# lab2_kochurin_buck.net
KiCad netlist of a schematic drawn in Altium Designer
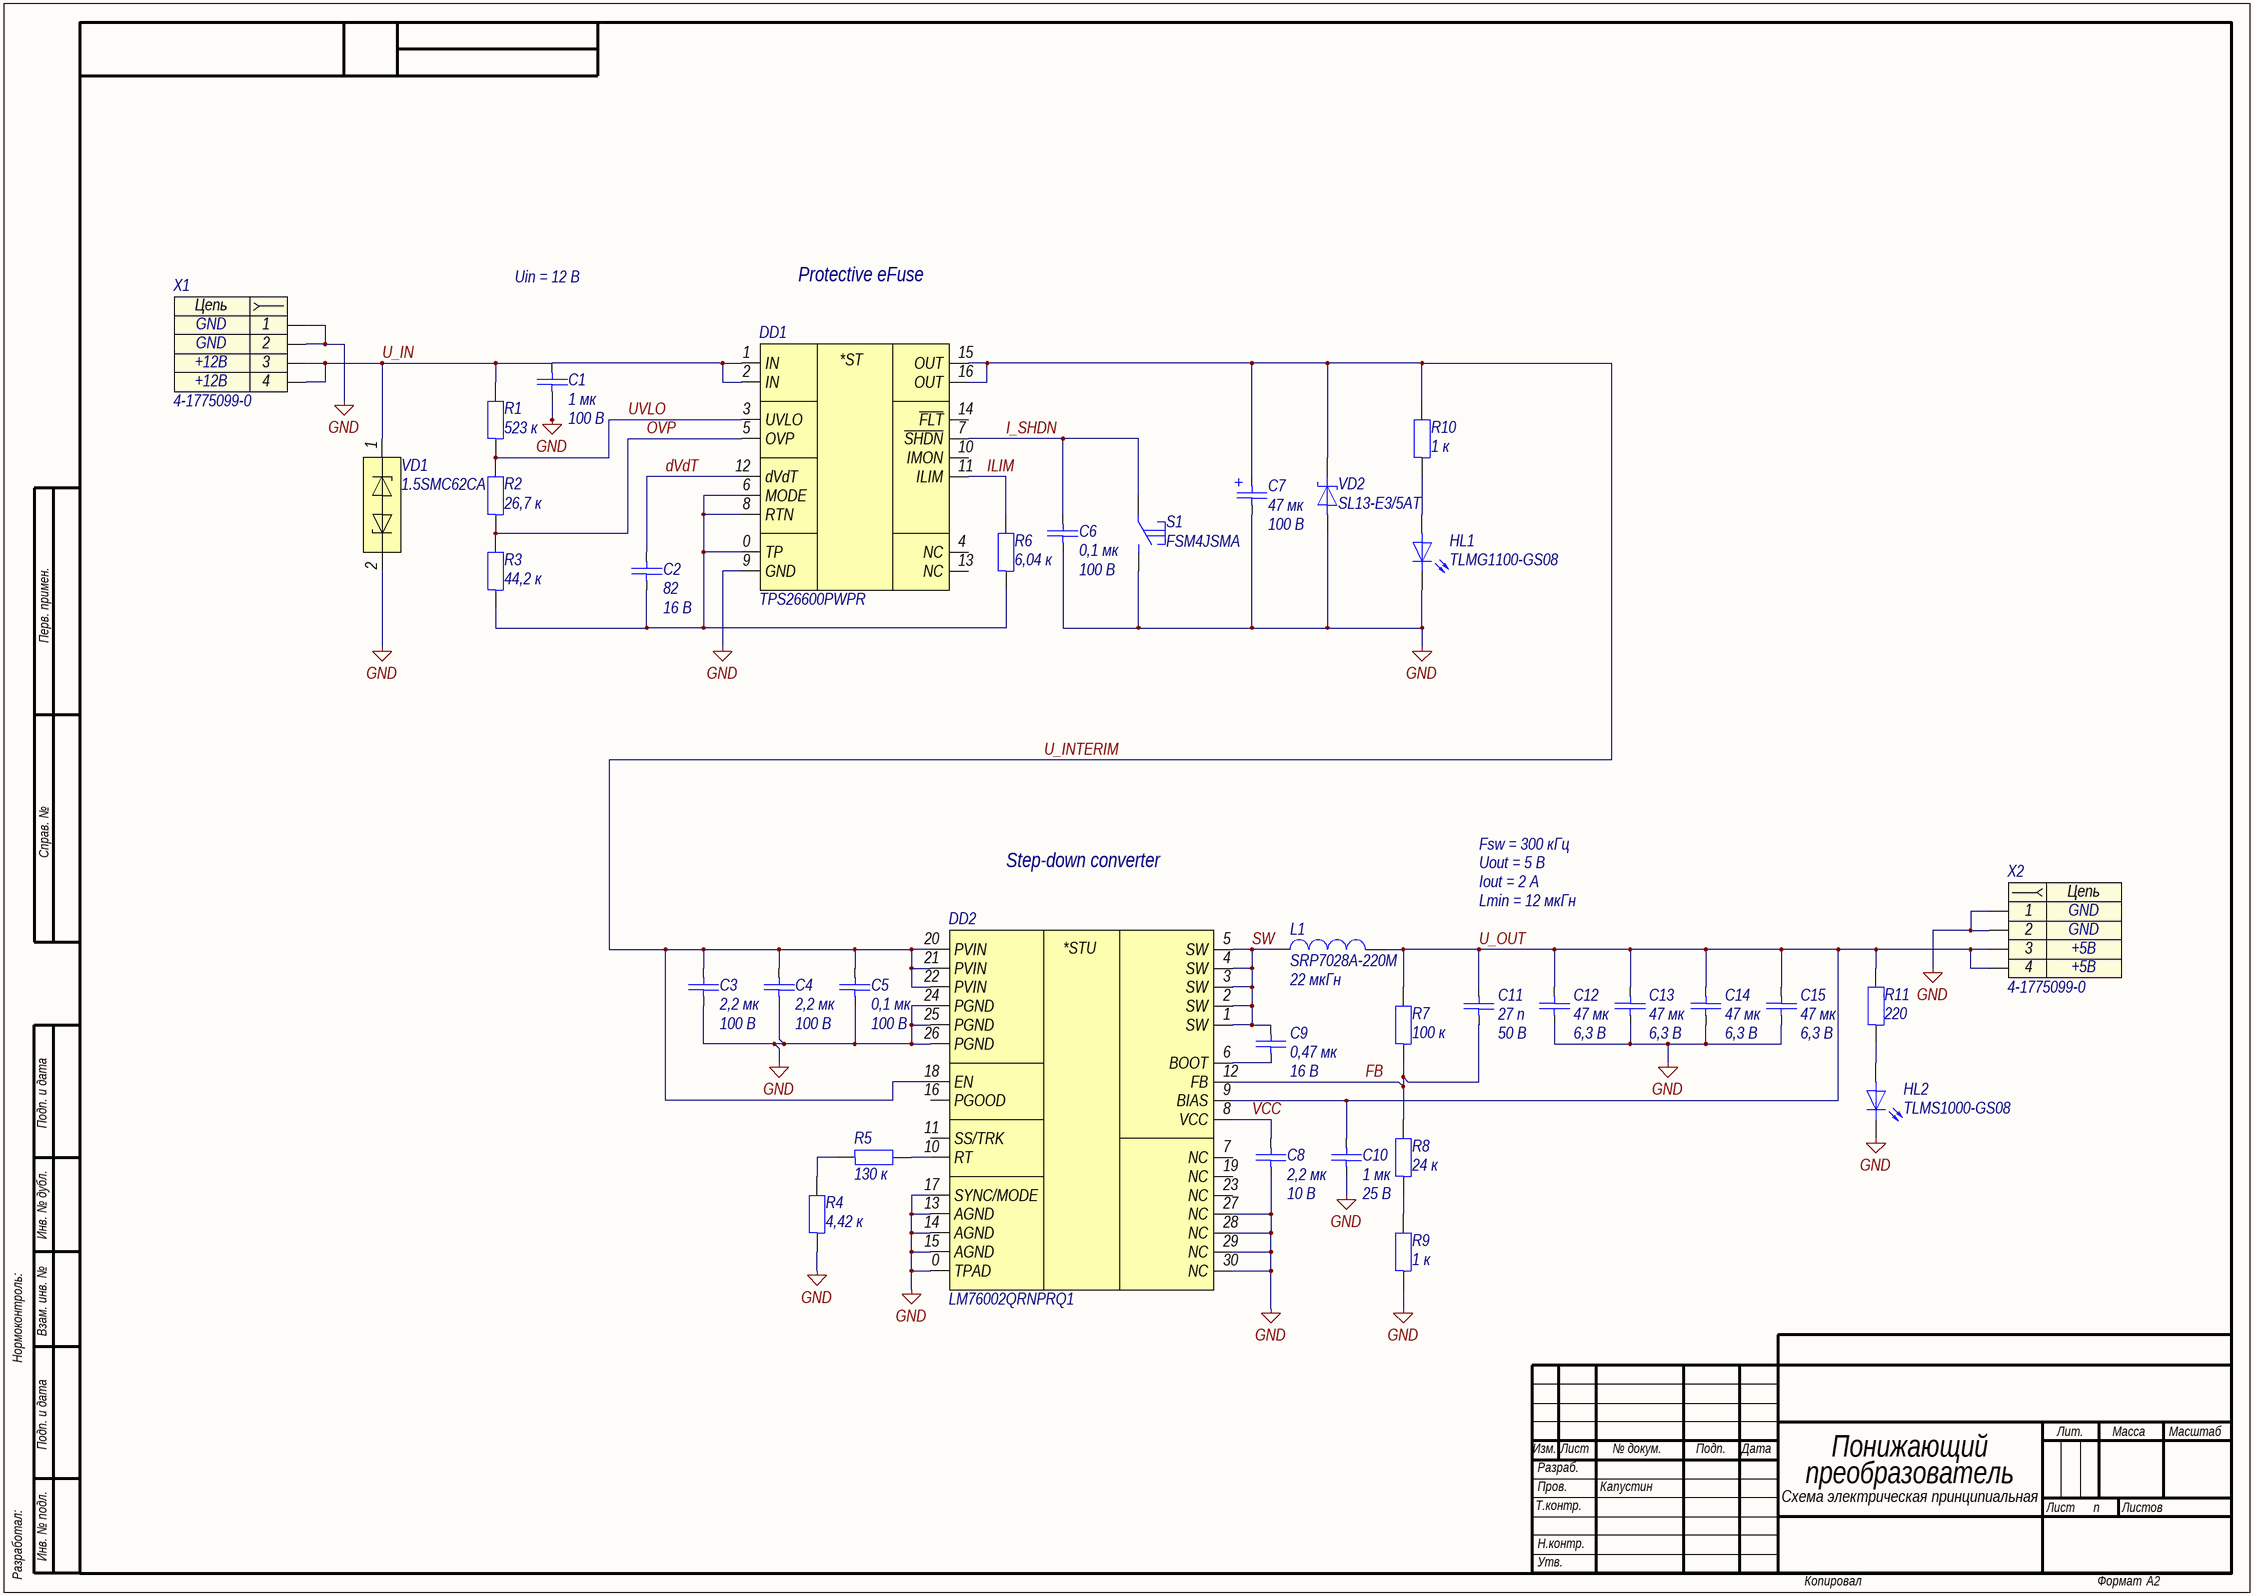
[diagram p0: lab2_kochurin_buck.SchDoc]

(export (version "E")
  (design (tool "Eeschema 10.0.6"))
  (components
    (comp (ref "C1")
      (value "1 мк")
      (footprint "C1206")
      (description "=Описание")
      (fields (field (name "НАПРЯЖЕНИЕ") "100 В"))
      (libsource (lib "Database_Students") (part "C-NONPOLAR"))
    )
    (comp (ref "C2")
      (value "82")
      (footprint "C0603")
      (description "=Описание")
      (fields (field (name "НАПРЯЖЕНИЕ") "16 В"))
      (libsource (lib "Database_Students") (part "C-NONPOLAR"))
    )
    (comp (ref "C3")
      (value "2,2 мк")
      (footprint "C1206")
      (description "=Описание")
      (fields (field (name "НАПРЯЖЕНИЕ") "100 В"))
      (libsource (lib "Database_Students") (part "C-NONPOLAR"))
    )
    (comp (ref "C4")
      (value "2,2 мк")
      (footprint "C1206")
      (description "=Описание")
      (fields (field (name "НАПРЯЖЕНИЕ") "100 В"))
      (libsource (lib "Database_Students") (part "C-NONPOLAR"))
    )
    (comp (ref "C5")
      (value "0,1 мк")
      (footprint "C0603")
      (description "=Описание")
      (fields (field (name "НАПРЯЖЕНИЕ") "100 В"))
      (libsource (lib "Database_Students") (part "C-NONPOLAR"))
    )
    (comp (ref "C6")
      (value "0,1 мк")
      (footprint "C0603")
      (description "=Описание")
      (fields (field (name "НАПРЯЖЕНИЕ") "100 В"))
      (libsource (lib "Database_Students") (part "C-NONPOLAR"))
    )
    (comp (ref "C7")
      (value "47 мк")
      (footprint "CAPAE-1000X1000X1200")
      (description "=Описание")
      (fields (field (name "НАПРЯЖЕНИЕ") "100 В"))
      (libsource (lib "Database_Students") (part "C-POLAR"))
    )
    (comp (ref "C8")
      (value "2,2 мк")
      (footprint "C0603")
      (description "=Описание")
      (fields (field (name "НАПРЯЖЕНИЕ") "10 В"))
      (libsource (lib "Database_Students") (part "C-NONPOLAR"))
    )
    (comp (ref "C9")
      (value "0,47 мк")
      (footprint "C0603")
      (description "=Описание")
      (fields (field (name "НАПРЯЖЕНИЕ") "16 В"))
      (libsource (lib "Database_Students") (part "C-NONPOLAR"))
    )
    (comp (ref "C10")
      (value "1 мк")
      (footprint "C0603")
      (description "=Описание")
      (fields (field (name "НАПРЯЖЕНИЕ") "25 В"))
      (libsource (lib "Database_Students") (part "C-NONPOLAR"))
    )
    (comp (ref "C11")
      (value "27 п")
      (footprint "C0402")
      (description "=Описание")
      (fields (field (name "НАПРЯЖЕНИЕ") "50 В"))
      (libsource (lib "Database_Students") (part "C-NONPOLAR"))
    )
    (comp (ref "C12")
      (value "47 мк")
      (footprint "C0603")
      (description "=Описание")
      (fields (field (name "НАПРЯЖЕНИЕ") "6,3 В"))
      (libsource (lib "Database_Students") (part "C-NONPOLAR"))
    )
    (comp (ref "C13")
      (value "47 мк")
      (footprint "C0603")
      (description "=Описание")
      (fields (field (name "НАПРЯЖЕНИЕ") "6,3 В"))
      (libsource (lib "Database_Students") (part "C-NONPOLAR"))
    )
    (comp (ref "C14")
      (value "47 мк")
      (footprint "C0603")
      (description "=Описание")
      (fields (field (name "НАПРЯЖЕНИЕ") "6,3 В"))
      (libsource (lib "Database_Students") (part "C-NONPOLAR"))
    )
    (comp (ref "C15")
      (value "47 мк")
      (footprint "C0603")
      (description "=Описание")
      (fields (field (name "НАПРЯЖЕНИЕ") "6,3 В"))
      (libsource (lib "Database_Students") (part "C-NONPOLAR"))
    )
    (comp (ref "DD1")
      (value "TPS26600PWPR")
      (footprint "HTSSOP-16")
      (description "=Описание")
      (libsource (lib "Database_Students") (part "TPS26600PWPR"))
    )
    (comp (ref "DD2")
      (value "LM76002QRNPRQ1")
      (footprint "WQFN-30")
      (description "=Описание")
      (libsource (lib "Database_Students") (part "LM76002QRNPRQ1"))
    )
    (comp (ref "HL1")
      (value "TLMG1100-GS08")
      (footprint "HL0603")
      (description "=Описание")
      (libsource (lib "Database_Students") (part "HL-COMMON"))
    )
    (comp (ref "HL2")
      (value "TLMS1000-GS08")
      (footprint "HL0603")
      (description "=Описание")
      (libsource (lib "Database_Students") (part "HL-COMMON"))
    )
    (comp (ref "L1")
      (value "SRP7028A-220M")
      (footprint "SRP-2-670X660X280")
      (description "=Описание")
      (fields (field (name "ИНДУКТИВНОСТЬ") "22 мкГн"))
      (libsource (lib "Database_Students") (part "INDUCTOR-COMMON"))
    )
    (comp (ref "R1")
      (value "523 к")
      (footprint "R0603")
      (description "=Описание")
      (libsource (lib "Database_Students") (part "R-COMMON"))
    )
    (comp (ref "R2")
      (value "26,7 к")
      (footprint "R0603")
      (description "=Описание")
      (libsource (lib "Database_Students") (part "R-COMMON"))
    )
    (comp (ref "R3")
      (value "44,2 к")
      (footprint "R0603")
      (description "=Описание")
      (libsource (lib "Database_Students") (part "R-COMMON"))
    )
    (comp (ref "R4")
      (value "4,42 к")
      (footprint "R0603")
      (description "=Описание")
      (libsource (lib "Database_Students") (part "R-COMMON"))
    )
    (comp (ref "R5")
      (value "130 к")
      (footprint "R0603")
      (description "=Описание")
      (libsource (lib "Database_Students") (part "R-COMMON"))
    )
    (comp (ref "R6")
      (value "6,04 к")
      (footprint "R0603")
      (description "=Описание")
      (libsource (lib "Database_Students") (part "R-COMMON"))
    )
    (comp (ref "R7")
      (value "100 к")
      (footprint "R0603")
      (description "=Описание")
      (libsource (lib "Database_Students") (part "R-COMMON"))
    )
    (comp (ref "R8")
      (value "24 к")
      (footprint "R0603")
      (description "=Описание")
      (libsource (lib "Database_Students") (part "R-COMMON"))
    )
    (comp (ref "R9")
      (value "1 к")
      (footprint "R0603")
      (description "=Описание")
      (libsource (lib "Database_Students") (part "R-COMMON"))
    )
    (comp (ref "R10")
      (value "1 к")
      (footprint "R1218")
      (description "=Описание")
      (libsource (lib "Database_Students") (part "R-COMMON"))
    )
    (comp (ref "R11")
      (value "220")
      (footprint "R0603")
      (description "=Описание")
      (libsource (lib "Database_Students") (part "R-COMMON"))
    )
    (comp (ref "S1")
      (value "FSM4JSMA")
      (footprint "FSM4JSMA")
      (description "=Описание")
      (libsource (lib "Database_Students") (part "BUTTON"))
    )
    (comp (ref "VD1")
      (value "1.5SMC62CA")
      (footprint "DO-214AB")
      (description "=Описание")
      (libsource (lib "Database_Students") (part "ZENER-BI-DIRECTIONAL"))
    )
    (comp (ref "VD2")
      (value "SL13-E3/5AT")
      (footprint "DO-214AC")
      (description "=Описание")
      (libsource (lib "Database_Students") (part "DIODE-SCHOTTKY"))
    )
    (comp (ref "X1")
      (value "4-1775099-0")
      (footprint "4-1775099-0")
      (description "=Описание")
      (libsource (lib "Database_Students") (part "HEADER-4-SCT"))
    )
    (comp (ref "X2")
      (value "4-1775099-0")
      (footprint "4-1775099-0")
      (description "=Описание")
      (libsource (lib "") (part "HEADER-4-SCT_1"))
    )
  )
  (nets
    (net (code "1") (name "/FB") (class "Default")
      (node (ref "C11") (pin "2") (pinfunction "2_2") (pintype "passive"))
      (node (ref "DD2") (pin "12") (pinfunction "FB_12") (pintype "passive"))
      (node (ref "R7") (pin "1") (pinfunction "1_1") (pintype "passive"))
      (node (ref "R8") (pin "2") (pinfunction "2_2") (pintype "passive"))
    )
    (net (code "2") (name "/ILIM") (class "Default")
      (node (ref "DD1") (pin "11") (pinfunction "ILIM_11") (pintype "passive"))
      (node (ref "R6") (pin "2") (pinfunction "2_2") (pintype "passive"))
    )
    (net (code "3") (name "/I_SHDN") (class "Default")
      (node (ref "C6") (pin "1") (pinfunction "1_1") (pintype "passive"))
      (node (ref "DD1") (pin "7") (pinfunction "~{SHDN}_7") (pintype "passive"))
      (node (ref "S1") (pin "1") (pinfunction "1_1") (pintype "passive"))
    )
    (net (code "4") (name "/OVP") (class "Default")
      (node (ref "DD1") (pin "5") (pinfunction "OVP_5") (pintype "passive"))
      (node (ref "R2") (pin "1") (pinfunction "1_1") (pintype "passive"))
      (node (ref "R3") (pin "2") (pinfunction "2_2") (pintype "passive"))
    )
    (net (code "5") (name "/SW") (class "Default")
      (node (ref "C9") (pin "1") (pinfunction "1_1") (pintype "passive"))
      (node (ref "DD2") (pin "1") (pinfunction "SW_1") (pintype "passive"))
      (node (ref "DD2") (pin "2") (pinfunction "SW_2") (pintype "passive"))
      (node (ref "DD2") (pin "3") (pinfunction "SW_3") (pintype "passive"))
      (node (ref "DD2") (pin "4") (pinfunction "SW_4") (pintype "passive"))
      (node (ref "DD2") (pin "5") (pinfunction "SW_5") (pintype "passive"))
      (node (ref "L1") (pin "1") (pinfunction "1_1") (pintype "passive"))
    )
    (net (code "6") (name "/UVLO") (class "Default")
      (node (ref "DD1") (pin "3") (pinfunction "UVLO_3") (pintype "passive"))
      (node (ref "R1") (pin "1") (pinfunction "1_1") (pintype "passive"))
      (node (ref "R2") (pin "2") (pinfunction "2_2") (pintype "passive"))
    )
    (net (code "7") (name "/U_IN") (class "Default")
      (node (ref "C1") (pin "1") (pinfunction "1_1") (pintype "passive"))
      (node (ref "DD1") (pin "1") (pinfunction "IN_1") (pintype "passive"))
      (node (ref "DD1") (pin "2") (pinfunction "IN_2") (pintype "passive"))
      (node (ref "R1") (pin "2") (pinfunction "2_2") (pintype "passive"))
      (node (ref "VD1") (pin "1") (pinfunction "1_1") (pintype "passive"))
      (node (ref "X1") (pin "3") (pinfunction "3_3") (pintype "passive"))
      (node (ref "X1") (pin "4") (pinfunction "4_4") (pintype "passive"))
    )
    (net (code "8") (name "/U_INTERIM") (class "Default")
      (node (ref "C3") (pin "1") (pinfunction "1_1") (pintype "passive"))
      (node (ref "C4") (pin "1") (pinfunction "1_1") (pintype "passive"))
      (node (ref "C5") (pin "1") (pinfunction "1_1") (pintype "passive"))
      (node (ref "C7") (pin "1") (pinfunction "1_1") (pintype "passive"))
      (node (ref "DD1") (pin "15") (pinfunction "OUT_15") (pintype "passive"))
      (node (ref "DD1") (pin "16") (pinfunction "OUT_16") (pintype "passive"))
      (node (ref "DD2") (pin "18") (pinfunction "EN_18") (pintype "passive"))
      (node (ref "DD2") (pin "20") (pinfunction "PVIN_20") (pintype "passive"))
      (node (ref "DD2") (pin "21") (pinfunction "PVIN_21") (pintype "passive"))
      (node (ref "DD2") (pin "22") (pinfunction "PVIN_22") (pintype "passive"))
      (node (ref "R10") (pin "2") (pinfunction "2_2") (pintype "passive"))
      (node (ref "VD2") (pin "1") (pinfunction "1_1") (pintype "passive"))
    )
    (net (code "9") (name "/U_OUT") (class "Default")
      (node (ref "C10") (pin "1") (pinfunction "1_1") (pintype "passive"))
      (node (ref "C11") (pin "1") (pinfunction "1_1") (pintype "passive"))
      (node (ref "C12") (pin "2") (pinfunction "2_2") (pintype "passive"))
      (node (ref "C13") (pin "2") (pinfunction "2_2") (pintype "passive"))
      (node (ref "C14") (pin "2") (pinfunction "2_2") (pintype "passive"))
      (node (ref "C15") (pin "2") (pinfunction "2_2") (pintype "passive"))
      (node (ref "DD2") (pin "9") (pinfunction "BIAS_9") (pintype "passive"))
      (node (ref "L1") (pin "2") (pinfunction "2_2") (pintype "passive"))
      (node (ref "R11") (pin "2") (pinfunction "2_2") (pintype "passive"))
      (node (ref "R7") (pin "2") (pinfunction "2_2") (pintype "passive"))
      (node (ref "X2") (pin "3") (pinfunction "3_3") (pintype "passive"))
      (node (ref "X2") (pin "4") (pinfunction "4_4") (pintype "passive"))
    )
    (net (code "10") (name "/VCC") (class "Default")
      (node (ref "C8") (pin "1") (pinfunction "1_1") (pintype "passive"))
      (node (ref "DD2") (pin "8") (pinfunction "VCC_8") (pintype "passive"))
    )
    (net (code "11") (name "/dVdT") (class "Default")
      (node (ref "C2") (pin "1") (pinfunction "1_1") (pintype "passive"))
      (node (ref "DD1") (pin "12") (pinfunction "dVdT_12") (pintype "passive"))
    )
    (net (code "12") (name "GND") (class "Default")
      (node (ref "C1") (pin "2") (pinfunction "2_2") (pintype "passive"))
      (node (ref "C10") (pin "2") (pinfunction "2_2") (pintype "passive"))
      (node (ref "C12") (pin "1") (pinfunction "1_1") (pintype "passive"))
      (node (ref "C13") (pin "1") (pinfunction "1_1") (pintype "passive"))
      (node (ref "C14") (pin "1") (pinfunction "1_1") (pintype "passive"))
      (node (ref "C15") (pin "1") (pinfunction "1_1") (pintype "passive"))
      (node (ref "C3") (pin "2") (pinfunction "2_2") (pintype "passive"))
      (node (ref "C4") (pin "2") (pinfunction "2_2") (pintype "passive"))
      (node (ref "C5") (pin "2") (pinfunction "2_2") (pintype "passive"))
      (node (ref "C6") (pin "2") (pinfunction "2_2") (pintype "passive"))
      (node (ref "C7") (pin "2") (pinfunction "2_2") (pintype "passive"))
      (node (ref "C8") (pin "2") (pinfunction "2_2") (pintype "passive"))
      (node (ref "DD1") (pin "9") (pinfunction "GND_9") (pintype "passive"))
      (node (ref "DD2") (pin "0") (pinfunction "TPAD_0") (pintype "passive"))
      (node (ref "DD2") (pin "13") (pinfunction "AGND_13") (pintype "passive"))
      (node (ref "DD2") (pin "14") (pinfunction "AGND_14") (pintype "passive"))
      (node (ref "DD2") (pin "15") (pinfunction "AGND_15") (pintype "passive"))
      (node (ref "DD2") (pin "17") (pinfunction "SYNC/MODE_17") (pintype "passive"))
      (node (ref "DD2") (pin "24") (pinfunction "PGND_24") (pintype "passive"))
      (node (ref "DD2") (pin "25") (pinfunction "PGND_25") (pintype "passive"))
      (node (ref "DD2") (pin "26") (pinfunction "PGND_26") (pintype "passive"))
      (node (ref "DD2") (pin "27") (pinfunction "NC_27") (pintype "passive"))
      (node (ref "DD2") (pin "28") (pinfunction "NC_28") (pintype "passive"))
      (node (ref "DD2") (pin "29") (pinfunction "NC_29") (pintype "passive"))
      (node (ref "DD2") (pin "30") (pinfunction "NC_30") (pintype "passive"))
      (node (ref "HL1") (pin "1") (pinfunction "1_1") (pintype "passive"))
      (node (ref "HL2") (pin "1") (pinfunction "1_1") (pintype "passive"))
      (node (ref "R4") (pin "1") (pinfunction "1_1") (pintype "passive"))
      (node (ref "R9") (pin "1") (pinfunction "1_1") (pintype "passive"))
      (node (ref "S1") (pin "2") (pinfunction "2_2") (pintype "passive"))
      (node (ref "VD1") (pin "2") (pinfunction "2_2") (pintype "passive"))
      (node (ref "VD2") (pin "2") (pinfunction "2_2") (pintype "passive"))
      (node (ref "X1") (pin "1") (pinfunction "1_1") (pintype "passive"))
      (node (ref "X1") (pin "2") (pinfunction "2_2") (pintype "passive"))
      (node (ref "X2") (pin "1") (pinfunction "1_1") (pintype "passive"))
      (node (ref "X2") (pin "2") (pinfunction "2_2") (pintype "passive"))
    )
    (net (code "13") (name "Net-(DD1-MODE)") (class "Default")
      (node (ref "C2") (pin "2") (pinfunction "2_2") (pintype "passive"))
      (node (ref "DD1") (pin "0") (pinfunction "TP_0") (pintype "passive"))
      (node (ref "DD1") (pin "6") (pinfunction "MODE_6") (pintype "passive"))
      (node (ref "DD1") (pin "8") (pinfunction "RTN_8") (pintype "passive"))
      (node (ref "R3") (pin "1") (pinfunction "1_1") (pintype "passive"))
      (node (ref "R6") (pin "1") (pinfunction "1_1") (pintype "passive"))
    )
    (net (code "14") (name "Net-(DD2-BOOT)") (class "Default")
      (node (ref "C9") (pin "2") (pinfunction "2_2") (pintype "passive"))
      (node (ref "DD2") (pin "6") (pinfunction "BOOT_6") (pintype "passive"))
    )
    (net (code "15") (name "Net-(DD2-RT)") (class "Default")
      (node (ref "DD2") (pin "10") (pinfunction "RT_10") (pintype "passive"))
      (node (ref "R5") (pin "2") (pinfunction "2_2") (pintype "passive"))
    )
    (net (code "16") (name "Net-(HL1-Pad2)") (class "Default")
      (node (ref "HL1") (pin "2") (pinfunction "2_2") (pintype "passive"))
      (node (ref "R10") (pin "1") (pinfunction "1_1") (pintype "passive"))
    )
    (net (code "17") (name "Net-(HL2-Pad2)") (class "Default")
      (node (ref "HL2") (pin "2") (pinfunction "2_2") (pintype "passive"))
      (node (ref "R11") (pin "1") (pinfunction "1_1") (pintype "passive"))
    )
    (net (code "18") (name "Net-(R4-Pad2)") (class "Default")
      (node (ref "R4") (pin "2") (pinfunction "2_2") (pintype "passive"))
      (node (ref "R5") (pin "1") (pinfunction "1_1") (pintype "passive"))
    )
    (net (code "19") (name "Net-(R8-Pad1)") (class "Default")
      (node (ref "R8") (pin "1") (pinfunction "1_1") (pintype "passive"))
      (node (ref "R9") (pin "2") (pinfunction "2_2") (pintype "passive"))
    )
    (net (code "20") (name "unconnected-(DD1-IMON-Pad10)") (class "Default")
      (node (ref "DD1") (pin "10") (pinfunction "IMON_10") (pintype "passive"))
    )
    (net (code "21") (name "unconnected-(DD1-NC-Pad4)") (class "Default")
      (node (ref "DD1") (pin "4") (pinfunction "NC_4") (pintype "passive"))
    )
    (net (code "22") (name "unconnected-(DD1-NC-Pad13)") (class "Default")
      (node (ref "DD1") (pin "13") (pinfunction "NC_13") (pintype "passive"))
    )
    (net (code "23") (name "unconnected-(DD1-~{FLT}-Pad14)") (class "Default")
      (node (ref "DD1") (pin "14") (pinfunction "~{FLT}_14") (pintype "passive"))
    )
    (net (code "24") (name "unconnected-(DD2-NC-Pad7)") (class "Default")
      (node (ref "DD2") (pin "7") (pinfunction "NC_7") (pintype "passive"))
    )
    (net (code "25") (name "unconnected-(DD2-NC-Pad19)") (class "Default")
      (node (ref "DD2") (pin "19") (pinfunction "NC_19") (pintype "passive"))
    )
    (net (code "26") (name "unconnected-(DD2-NC-Pad23)") (class "Default")
      (node (ref "DD2") (pin "23") (pinfunction "NC_23") (pintype "passive"))
    )
    (net (code "27") (name "unconnected-(DD2-PGOOD-Pad16)") (class "Default")
      (node (ref "DD2") (pin "16") (pinfunction "PGOOD_16") (pintype "passive"))
    )
    (net (code "28") (name "unconnected-(DD2-SS{slash}TRK-Pad11)") (class "Default")
      (node (ref "DD2") (pin "11") (pinfunction "SS/TRK_11") (pintype "passive"))
    )
  )
)
